# Pre_Charge_Interface.net
KiCad netlist of a schematic drawn in Altium Designer
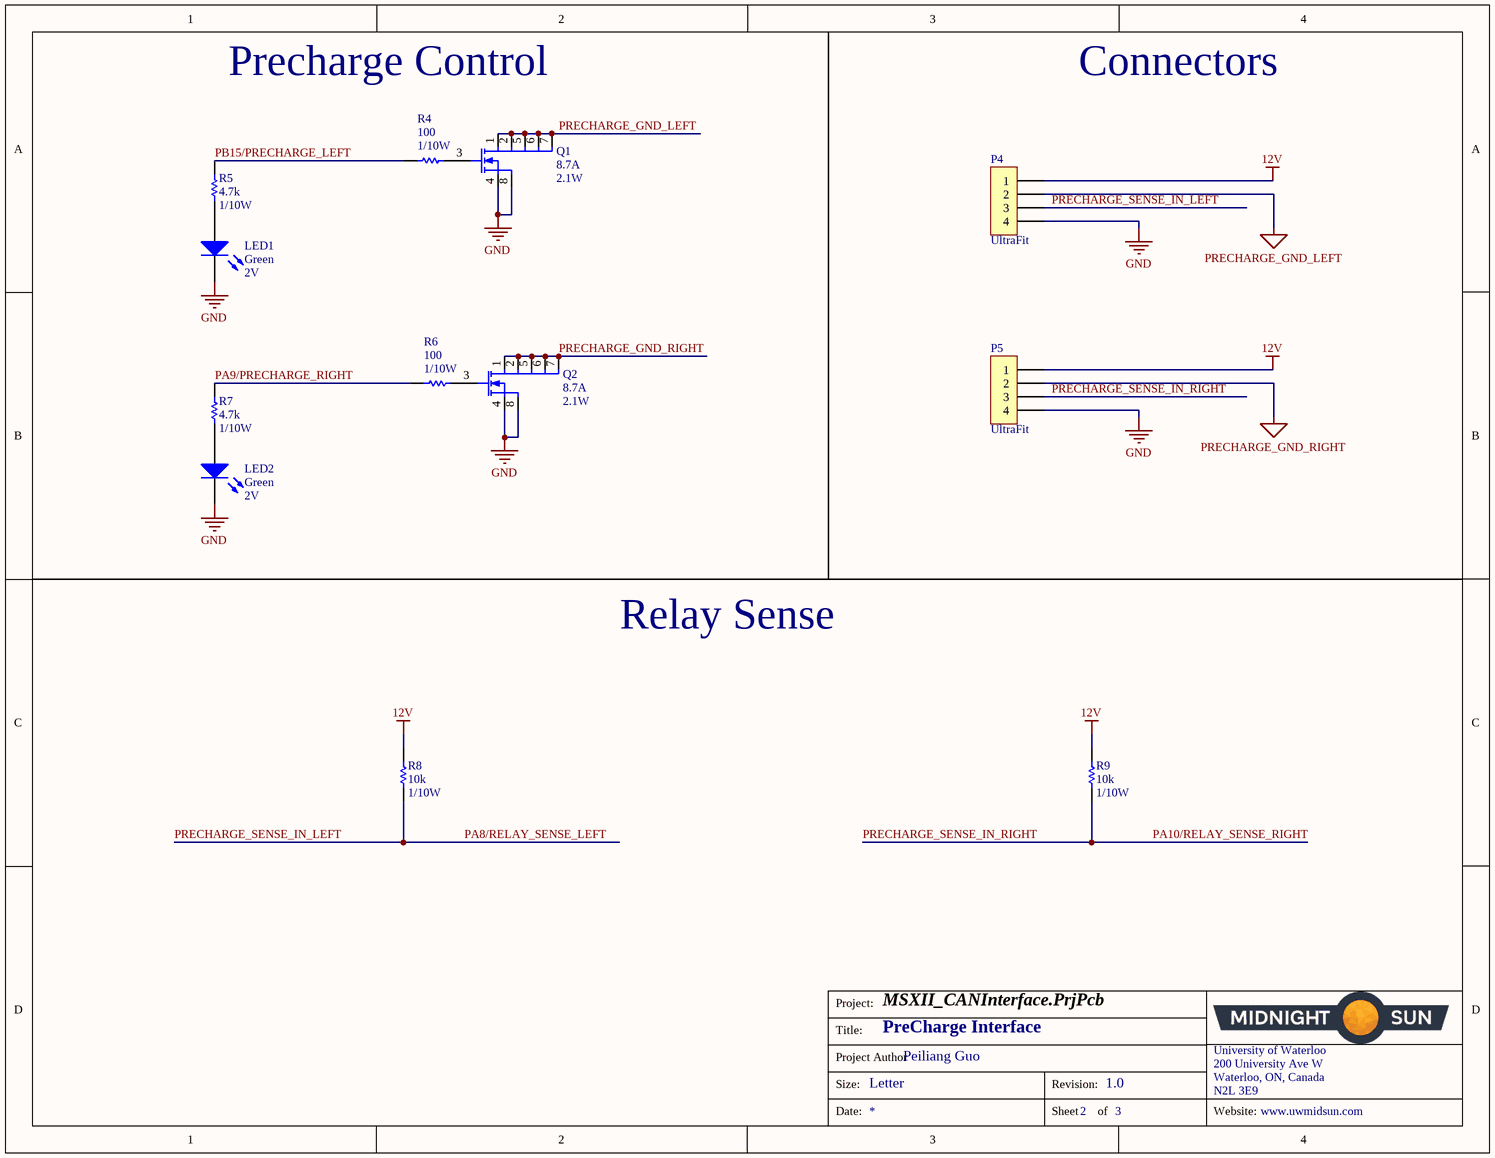
[diagram p0: Pre_Charge_Interface.SchDoc]

(export (version "E")
  (design (tool "Eeschema 10.0.6"))
  (components
    (comp (ref "LED1")
      (value "LED GREEN CLEAR 2V 0603")
      (footprint "LED_0603")
      (description "Green 572nm LED Indication - Discrete 2V 0603 (1608 Metric)")
      (fields
        (field (name "MANUFACTURER") "Wurth Electronics Inc.")
        (field (name "MANUFACTURER PART NUMBER") "150060VS75000")
        (field (name "COLOR") "Green")
        (field (name "VOLTAGE - FORWARD (VF) (TYP)") "2V")
      )
      (libsource (lib "Schematic Diagrams") (part "LED GREEN CLEAR 2V 0603"))
    )
    (comp (ref "LED2")
      (value "LED GREEN CLEAR 2V 0603")
      (footprint "LED_0603")
      (description "Green 572nm LED Indication - Discrete 2V 0603 (1608 Metric)")
      (fields
        (field (name "MANUFACTURER") "Wurth Electronics Inc.")
        (field (name "MANUFACTURER PART NUMBER") "150060VS75000")
        (field (name "COLOR") "Green")
        (field (name "VOLTAGE - FORWARD (VF) (TYP)") "2V")
      )
      (libsource (lib "Schematic Diagrams") (part "LED GREEN CLEAR 2V 0603"))
    )
    (comp (ref "P4")
      (value "CONN 4POS ULTRA-FIT 0.138\"")
      (footprint "CONN, 4POS ULTRA-FIT")
      (description "4 Positions Header Connector 0.138\" (3.50mm) Through Hole Tin")
      (fields (field (name "VOLTAGE") "400V") (field (name "SERIES") "UltraFit"))
      (libsource (lib "Schematic Diagrams") (part "CONN 4POS ULTRA-FIT 0.138{dblquote}"))
    )
    (comp (ref "P5")
      (value "CONN 4POS ULTRA-FIT 0.138\"")
      (footprint "CONN, 4POS ULTRA-FIT")
      (description "4 Positions Header Connector 0.138\" (3.50mm) Through Hole Tin")
      (fields (field (name "VOLTAGE") "400V") (field (name "SERIES") "UltraFit"))
      (libsource (lib "Schematic Diagrams") (part "CONN 4POS ULTRA-FIT 0.138{dblquote}"))
    )
    (comp (ref "Q1")
      (value "MOSFET N-CH 30V 8.7A 2.1W 6-PQFN (2x2)")
      (footprint "MOSFET N-CH 30V 12A 2mmx2mm PQFN")
      (fields
        (field (name "CURRENT - CONTINUOUS DRAIN (ID) @ 25°C") "8.7A")
        (field (name "POWER DISSIPATION (MAX)") "2.1W")
      )
      (libsource (lib "Schematic Diagrams") (part "MOSFET N-CH 30V 8.7A 2.1W 6-PQFN (2x2)"))
    )
    (comp (ref "Q2")
      (value "MOSFET N-CH 30V 8.7A 2.1W 6-PQFN (2x2)")
      (footprint "MOSFET N-CH 30V 12A 2mmx2mm PQFN")
      (fields
        (field (name "CURRENT - CONTINUOUS DRAIN (ID) @ 25°C") "8.7A")
        (field (name "POWER DISSIPATION (MAX)") "2.1W")
      )
      (libsource (lib "Schematic Diagrams") (part "MOSFET N-CH 30V 8.7A 2.1W 6-PQFN (2x2)"))
    )
    (comp (ref "R4")
      (value "RES 100 OHM 1% 1/10W 0603")
      (footprint "RES, 0603")
      (description "100 Ohm ±1% 0.1W, 1/10W Chip Resistor 0603 (1608 Metric) Moisture Resistant Thick Film")
      (fields
        (field (name "TOLERANCE") "±1%")
        (field (name "RESISTANCE") "100")
        (field (name "POWER") "1/10W")
      )
      (libsource (lib "Schematic Diagrams") (part "RES 100 OHM 1% 1/10W 0603"))
    )
    (comp (ref "R5")
      (value "RES 4.7K OHM 1% 1/10W 0603")
      (footprint "RES, 0603")
      (description "4.7k Ohm ±1% 0.1W, 1/10W Chip Resistor 0603 (1608 Metric) Moisture Resistant Thick Film")
      (fields
        (field (name "TOLERANCE") "±1%")
        (field (name "RESISTANCE (OHMS)") "4.7k")
        (field (name "POWER (WATTS)") "1/10W")
      )
      (libsource (lib "Schematic Diagrams") (part "RES 4.7K OHM 1% 1/10W 0603"))
    )
    (comp (ref "R6")
      (value "RES 100 OHM 1% 1/10W 0603")
      (footprint "RES, 0603")
      (description "100 Ohm ±1% 0.1W, 1/10W Chip Resistor 0603 (1608 Metric) Moisture Resistant Thick Film")
      (fields
        (field (name "TOLERANCE") "±1%")
        (field (name "RESISTANCE") "100")
        (field (name "POWER") "1/10W")
      )
      (libsource (lib "Schematic Diagrams") (part "RES 100 OHM 1% 1/10W 0603"))
    )
    (comp (ref "R7")
      (value "RES 4.7K OHM 1% 1/10W 0603")
      (footprint "RES, 0603")
      (description "4.7k Ohm ±1% 0.1W, 1/10W Chip Resistor 0603 (1608 Metric) Moisture Resistant Thick Film")
      (fields
        (field (name "TOLERANCE") "±1%")
        (field (name "RESISTANCE (OHMS)") "4.7k")
        (field (name "POWER (WATTS)") "1/10W")
      )
      (libsource (lib "Schematic Diagrams") (part "RES 4.7K OHM 1% 1/10W 0603"))
    )
    (comp (ref "R8")
      (value "RES 10K OHM 1% 1/10W 0603")
      (footprint "RES, 0603")
      (description "RES SMD 10K OHM 1% 1/10W 0603")
      (fields
        (field (name "TOLERANCE") "±1%")
        (field (name "RESISTANCE") "10k")
        (field (name "POWER") "1/10W")
      )
      (libsource (lib "Schematic Diagrams") (part "RES 10K OHM 1% 1/10W 0603"))
    )
    (comp (ref "R9")
      (value "RES 10K OHM 1% 1/10W 0603")
      (footprint "RES, 0603")
      (description "RES SMD 10K OHM 1% 1/10W 0603")
      (fields
        (field (name "TOLERANCE") "±1%")
        (field (name "RESISTANCE") "10k")
        (field (name "POWER") "1/10W")
      )
      (libsource (lib "Schematic Diagrams") (part "RES 10K OHM 1% 1/10W 0603"))
    )
  )
  (nets
    (net (code "1") (name "/PA8{slash}RELAY_SENSE_LEFT") (class "Default")
      (node (ref "P4") (pin "3") (pinfunction "3_3") (pintype "passive"))
      (node (ref "R8") (pin "2") (pinfunction "2_2") (pintype "passive"))
    )
    (net (code "2") (name "/PA9{slash}PRECHARGE_RIGHT") (class "Default")
      (node (ref "R6") (pin "1") (pinfunction "1_1") (pintype "passive"))
      (node (ref "R7") (pin "1") (pinfunction "1_1") (pintype "passive"))
    )
    (net (code "3") (name "/PA10{slash}RELAY_SENSE_RIGHT") (class "Default")
      (node (ref "P5") (pin "3") (pinfunction "3_3") (pintype "passive"))
      (node (ref "R9") (pin "2") (pinfunction "2_2") (pintype "passive"))
    )
    (net (code "4") (name "/PB15{slash}PRECHARGE_LEFT") (class "Default")
      (node (ref "R4") (pin "1") (pinfunction "1_1") (pintype "passive"))
      (node (ref "R5") (pin "1") (pinfunction "1_1") (pintype "passive"))
    )
    (net (code "5") (name "12V") (class "Default")
      (node (ref "P4") (pin "1") (pinfunction "1_1") (pintype "passive"))
      (node (ref "P5") (pin "1") (pinfunction "1_1") (pintype "passive"))
      (node (ref "R8") (pin "1") (pinfunction "1_1") (pintype "passive"))
      (node (ref "R9") (pin "1") (pinfunction "1_1") (pintype "passive"))
    )
    (net (code "6") (name "GND") (class "Default")
      (node (ref "LED1") (pin "2") (pinfunction "K_2") (pintype "passive"))
      (node (ref "LED2") (pin "2") (pinfunction "K_2") (pintype "passive"))
      (node (ref "P4") (pin "4") (pinfunction "4_4") (pintype "passive"))
      (node (ref "P5") (pin "4") (pinfunction "4_4") (pintype "passive"))
      (node (ref "Q1") (pin "4") (pinfunction "S_4") (pintype "passive"))
      (node (ref "Q1") (pin "8") (pinfunction "S_8") (pintype "passive"))
      (node (ref "Q2") (pin "4") (pinfunction "S_4") (pintype "passive"))
      (node (ref "Q2") (pin "8") (pinfunction "S_8") (pintype "passive"))
    )
    (net (code "7") (name "Net-(LED1-A)") (class "Default")
      (node (ref "LED1") (pin "1") (pinfunction "A_1") (pintype "passive"))
      (node (ref "R5") (pin "2") (pinfunction "2_2") (pintype "passive"))
    )
    (net (code "8") (name "Net-(LED2-A)") (class "Default")
      (node (ref "LED2") (pin "1") (pinfunction "A_1") (pintype "passive"))
      (node (ref "R7") (pin "2") (pinfunction "2_2") (pintype "passive"))
    )
    (net (code "9") (name "Net-(Q1-G)") (class "Default")
      (node (ref "Q1") (pin "3") (pinfunction "G_3") (pintype "passive"))
      (node (ref "R4") (pin "2") (pinfunction "2_2") (pintype "passive"))
    )
    (net (code "10") (name "Net-(Q2-G)") (class "Default")
      (node (ref "Q2") (pin "3") (pinfunction "G_3") (pintype "passive"))
      (node (ref "R6") (pin "2") (pinfunction "2_2") (pintype "passive"))
    )
    (net (code "11") (name "PRECHARGE_GND_LEFT") (class "Default")
      (node (ref "P4") (pin "2") (pinfunction "2_2") (pintype "passive"))
      (node (ref "Q1") (pin "1") (pinfunction "D_1") (pintype "passive"))
      (node (ref "Q1") (pin "2") (pinfunction "D_2") (pintype "passive"))
      (node (ref "Q1") (pin "5") (pinfunction "D_5") (pintype "passive"))
      (node (ref "Q1") (pin "6") (pinfunction "D_6") (pintype "passive"))
      (node (ref "Q1") (pin "7") (pinfunction "D_7") (pintype "passive"))
    )
    (net (code "12") (name "PRECHARGE_GND_RIGHT") (class "Default")
      (node (ref "P5") (pin "2") (pinfunction "2_2") (pintype "passive"))
      (node (ref "Q2") (pin "1") (pinfunction "D_1") (pintype "passive"))
      (node (ref "Q2") (pin "2") (pinfunction "D_2") (pintype "passive"))
      (node (ref "Q2") (pin "5") (pinfunction "D_5") (pintype "passive"))
      (node (ref "Q2") (pin "6") (pinfunction "D_6") (pintype "passive"))
      (node (ref "Q2") (pin "7") (pinfunction "D_7") (pintype "passive"))
    )
  )
)
